# M700X.net
KiCad netlist of a schematic drawn in EAGLE
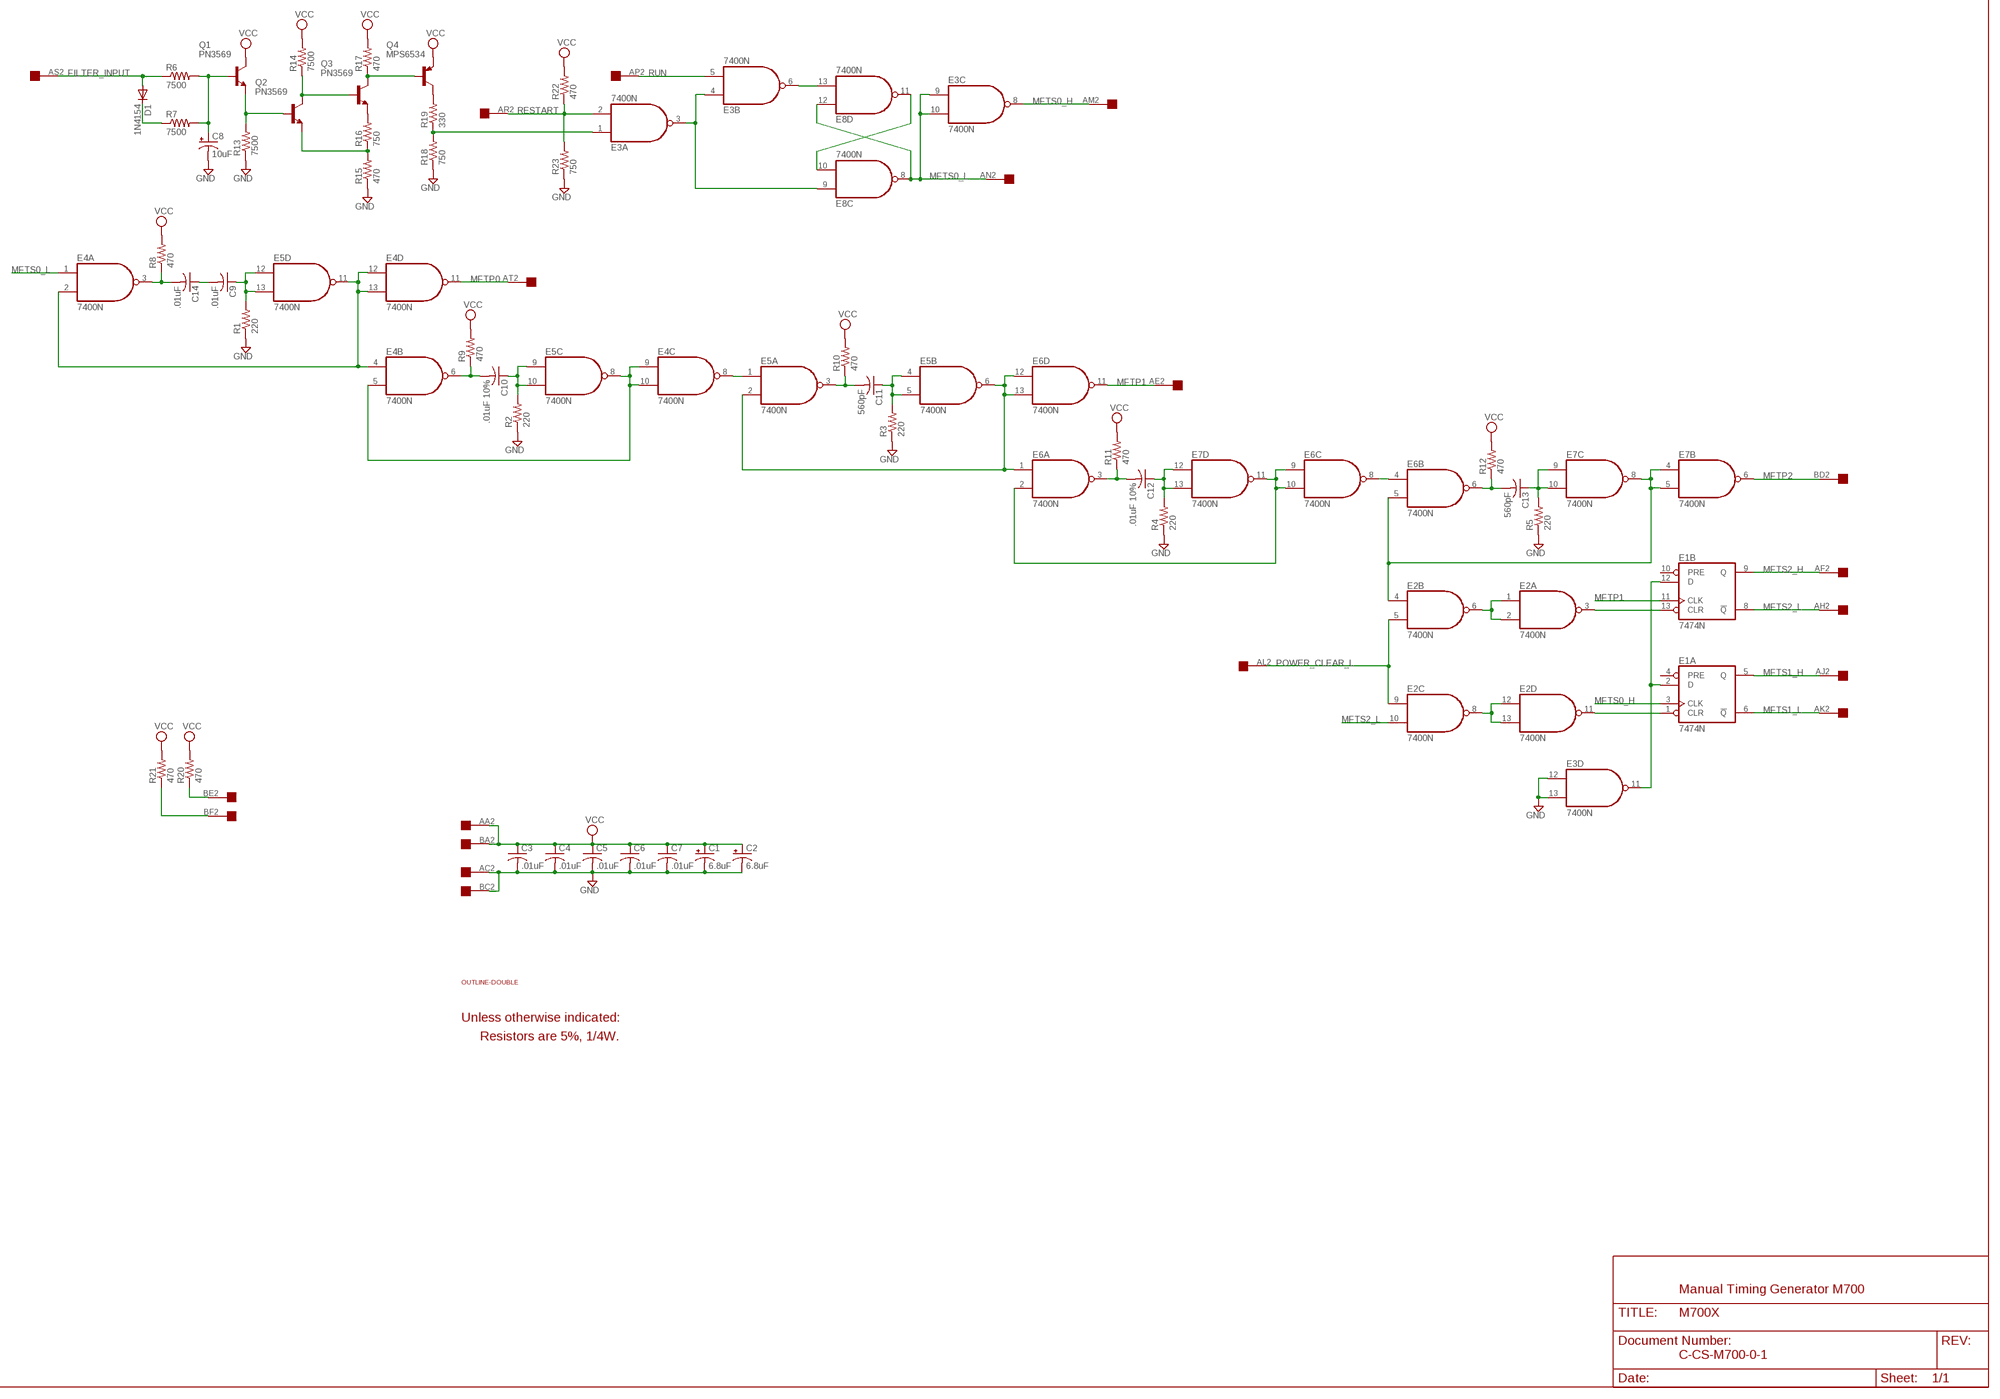
[diagram p0: schematic, sheet 1]

(export (version "E")
  (design (tool "Eeschema 10.0.6"))
  (components
    (comp (ref "C1")
      (value "6.8uF")
      (footprint "eagle-import:E12-8")
      (libsource (lib "eagle-import") (part "CPOL-USE20-8AXIAL"))
    )
    (comp (ref "C2")
      (value "6.8uF")
      (footprint "eagle-import:E12-8")
      (libsource (lib "eagle-import") (part "CPOL-USE20-8AXIAL"))
    )
    (comp (ref "C3")
      (value ".01uF")
      (footprint "eagle-import:C050-025X075")
      (libsource (lib "eagle-import") (part "C-US050-025X075"))
    )
    (comp (ref "C4")
      (value ".01uF")
      (footprint "eagle-import:C050-025X075")
      (libsource (lib "eagle-import") (part "C-US050-025X075"))
    )
    (comp (ref "C5")
      (value ".01uF")
      (footprint "eagle-import:C050-025X075")
      (libsource (lib "eagle-import") (part "C-US050-025X075"))
    )
    (comp (ref "C6")
      (value ".01uF")
      (footprint "eagle-import:C050-025X075")
      (libsource (lib "eagle-import") (part "C-US050-025X075"))
    )
    (comp (ref "C7")
      (value ".01uF")
      (footprint "eagle-import:C050-025X075")
      (libsource (lib "eagle-import") (part "C-US050-025X075"))
    )
    (comp (ref "C8")
      (value "10uF")
      (footprint "eagle-import:E12-8")
      (libsource (lib "eagle-import") (part "CPOL-USE20-8AXIAL"))
    )
    (comp (ref "C9")
      (value ".01uF")
      (footprint "eagle-import:C150-054X183")
      (libsource (lib "eagle-import") (part "C-US150-054X183"))
    )
    (comp (ref "C10")
      (value ".01uF 10%")
      (footprint "eagle-import:C150-054X183")
      (libsource (lib "eagle-import") (part "C-US150-054X183"))
    )
    (comp (ref "C11")
      (value "560pF")
      (footprint "eagle-import:C050-025X075")
      (libsource (lib "eagle-import") (part "C-US050-025X075"))
    )
    (comp (ref "C12")
      (value ".01uF 10%")
      (footprint "eagle-import:C150-054X183")
      (libsource (lib "eagle-import") (part "C-US150-054X183"))
    )
    (comp (ref "C13")
      (value "560pF")
      (footprint "eagle-import:C050-025X075")
      (libsource (lib "eagle-import") (part "C-US050-025X075"))
    )
    (comp (ref "C14")
      (value ".01uF")
      (footprint "eagle-import:C150-054X183")
      (libsource (lib "eagle-import") (part "C-US150-054X183"))
    )
    (comp (ref "D1")
      (value "1N4154")
      (footprint "eagle-import:DO35-10")
      (libsource (lib "eagle-import") (part "1N4148DO35-10"))
    )
    (comp (ref "E1")
      (value "7474N")
      (footprint "eagle-import:DIL14")
      (libsource (lib "eagle-import") (part "7474NS"))
    )
    (comp (ref "E2")
      (value "7400N")
      (footprint "eagle-import:DIL14")
      (libsource (lib "eagle-import") (part "7400N"))
    )
    (comp (ref "E3")
      (value "7400N")
      (footprint "eagle-import:DIL14")
      (libsource (lib "eagle-import") (part "7400N"))
    )
    (comp (ref "E4")
      (value "7400N")
      (footprint "eagle-import:DIL14")
      (libsource (lib "eagle-import") (part "7400N"))
    )
    (comp (ref "E5")
      (value "7400N")
      (footprint "eagle-import:DIL14")
      (libsource (lib "eagle-import") (part "7400N"))
    )
    (comp (ref "E6")
      (value "7400N")
      (footprint "eagle-import:DIL14")
      (libsource (lib "eagle-import") (part "7400N"))
    )
    (comp (ref "E7")
      (value "7400N")
      (footprint "eagle-import:DIL14")
      (libsource (lib "eagle-import") (part "7400N"))
    )
    (comp (ref "E8")
      (value "7400N")
      (footprint "eagle-import:DIL14")
      (libsource (lib "eagle-import") (part "7400N"))
    )
    (comp (ref "Q1")
      (value "PN3569")
      (footprint "eagle-import:TO5")
      (libsource (lib "eagle-import") (part "2N2102"))
    )
    (comp (ref "Q2")
      (value "PN3569")
      (footprint "eagle-import:TO5")
      (libsource (lib "eagle-import") (part "2N2102"))
    )
    (comp (ref "Q3")
      (value "PN3569")
      (footprint "eagle-import:TO5")
      (libsource (lib "eagle-import") (part "2N2102"))
    )
    (comp (ref "Q4")
      (value "MPS6534")
      (footprint "eagle-import:TO5")
      (libsource (lib "eagle-import") (part "2N2905"))
    )
    (comp (ref "R1")
      (value "220")
      (footprint "eagle-import:0207_10")
      (libsource (lib "eagle-import") (part "R-US_0207/10"))
    )
    (comp (ref "R2")
      (value "220")
      (footprint "eagle-import:0207_10")
      (libsource (lib "eagle-import") (part "R-US_0207/10"))
    )
    (comp (ref "R3")
      (value "220")
      (footprint "eagle-import:0207_10")
      (libsource (lib "eagle-import") (part "R-US_0207/10"))
    )
    (comp (ref "R4")
      (value "220")
      (footprint "eagle-import:0207_10")
      (libsource (lib "eagle-import") (part "R-US_0207/10"))
    )
    (comp (ref "R5")
      (value "220")
      (footprint "eagle-import:0207_10")
      (libsource (lib "eagle-import") (part "R-US_0207/10"))
    )
    (comp (ref "R6")
      (value "7500")
      (footprint "eagle-import:0207_10")
      (libsource (lib "eagle-import") (part "R-US_0207/10"))
    )
    (comp (ref "R7")
      (value "7500")
      (footprint "eagle-import:0207_10")
      (libsource (lib "eagle-import") (part "R-US_0207/10"))
    )
    (comp (ref "R8")
      (value "470")
      (footprint "eagle-import:0207_10")
      (libsource (lib "eagle-import") (part "R-US_0207/10"))
    )
    (comp (ref "R9")
      (value "470")
      (footprint "eagle-import:0207_10")
      (libsource (lib "eagle-import") (part "R-US_0207/10"))
    )
    (comp (ref "R10")
      (value "470")
      (footprint "eagle-import:0207_10")
      (libsource (lib "eagle-import") (part "R-US_0207/10"))
    )
    (comp (ref "R11")
      (value "470")
      (footprint "eagle-import:0207_10")
      (libsource (lib "eagle-import") (part "R-US_0207/10"))
    )
    (comp (ref "R12")
      (value "470")
      (footprint "eagle-import:0207_10")
      (libsource (lib "eagle-import") (part "R-US_0207/10"))
    )
    (comp (ref "R13")
      (value "7500")
      (footprint "eagle-import:0207_10")
      (libsource (lib "eagle-import") (part "R-US_0207/10"))
    )
    (comp (ref "R14")
      (value "7500")
      (footprint "eagle-import:0207_10")
      (libsource (lib "eagle-import") (part "R-US_0207/10"))
    )
    (comp (ref "R15")
      (value "470")
      (footprint "eagle-import:0207_10")
      (libsource (lib "eagle-import") (part "R-US_0207/10"))
    )
    (comp (ref "R16")
      (value "750")
      (footprint "eagle-import:0207_10")
      (libsource (lib "eagle-import") (part "R-US_0207/10"))
    )
    (comp (ref "R17")
      (value "470")
      (footprint "eagle-import:0207_10")
      (libsource (lib "eagle-import") (part "R-US_0207/10"))
    )
    (comp (ref "R18")
      (value "750")
      (footprint "eagle-import:0207_10")
      (libsource (lib "eagle-import") (part "R-US_0207/10"))
    )
    (comp (ref "R19")
      (value "330")
      (footprint "eagle-import:0207_10")
      (libsource (lib "eagle-import") (part "R-US_0207/10"))
    )
    (comp (ref "R20")
      (value "470")
      (footprint "eagle-import:0207_10")
      (libsource (lib "eagle-import") (part "R-US_0207/10"))
    )
    (comp (ref "R21")
      (value "470")
      (footprint "eagle-import:0207_10")
      (libsource (lib "eagle-import") (part "R-US_0207/10"))
    )
    (comp (ref "R22")
      (value "470")
      (footprint "eagle-import:0207_10")
      (libsource (lib "eagle-import") (part "R-US_0207/10"))
    )
    (comp (ref "R23")
      (value "750")
      (footprint "eagle-import:0207_10")
      (libsource (lib "eagle-import") (part "R-US_0207/10"))
    )
    (comp (ref "U$1")
      (value "DOUBLE")
      (footprint "eagle-import:EDGE-CON4")
      (libsource (lib "eagle-import") (part "DOUBLE"))
    )
    (comp (ref "U$2")
      (value "OUTLINE-DOUBLE")
      (footprint "eagle-import:DOUBLE")
      (libsource (lib "eagle-import") (part "OUTLINE-DOUBLE"))
    )
  )
  (nets
    (net (code "1") (name "/FILTER_INPUT") (class "Default")
      (node (ref "D1") (pin "A") (pinfunction "A_A") (pintype "passive"))
      (node (ref "R6") (pin "1") (pinfunction "1_1") (pintype "passive"))
      (node (ref "U$1") (pin "AS2") (pinfunction "1_AS2") (pintype "bidirectional"))
    )
    (net (code "2") (name "/MFTP0") (class "Default")
      (node (ref "E4") (pin "11") (pinfunction "O_11") (pintype "output"))
      (node (ref "U$1") (pin "AT2") (pinfunction "1_AT2") (pintype "bidirectional"))
    )
    (net (code "3") (name "/MFTP1") (class "Default")
      (node (ref "E1") (pin "11") (pinfunction "CLK_11") (pintype "input"))
      (node (ref "E6") (pin "11") (pinfunction "O_11") (pintype "output"))
      (node (ref "U$1") (pin "AE2") (pinfunction "1_AE2") (pintype "bidirectional"))
    )
    (net (code "4") (name "/MFTP2") (class "Default")
      (node (ref "E7") (pin "6") (pinfunction "O_6") (pintype "output"))
      (node (ref "U$1") (pin "BD2") (pinfunction "1_BD2") (pintype "bidirectional"))
    )
    (net (code "5") (name "/MFTS0_H") (class "Default")
      (node (ref "E1") (pin "3") (pinfunction "CLK_3") (pintype "input"))
      (node (ref "E3") (pin "8") (pinfunction "O_8") (pintype "output"))
      (node (ref "U$1") (pin "AM2") (pinfunction "1_AM2") (pintype "bidirectional"))
    )
    (net (code "6") (name "/MFTS0_L") (class "Default")
      (node (ref "E3") (pin "10") (pinfunction "I1_10") (pintype "input"))
      (node (ref "E3") (pin "9") (pinfunction "I0_9") (pintype "input"))
      (node (ref "E4") (pin "1") (pinfunction "I0_1") (pintype "input"))
      (node (ref "E8") (pin "12") (pinfunction "I0_12") (pintype "input"))
      (node (ref "E8") (pin "8") (pinfunction "O_8") (pintype "output"))
      (node (ref "U$1") (pin "AN2") (pinfunction "1_AN2") (pintype "bidirectional"))
    )
    (net (code "7") (name "/MFTS1_H") (class "Default")
      (node (ref "E1") (pin "5") (pinfunction "Q_5") (pintype "output"))
      (node (ref "U$1") (pin "AJ2") (pinfunction "1_AJ2") (pintype "bidirectional"))
    )
    (net (code "8") (name "/MFTS1_L") (class "Default")
      (node (ref "E1") (pin "6") (pinfunction "~{Q}_6") (pintype "output"))
      (node (ref "U$1") (pin "AK2") (pinfunction "1_AK2") (pintype "bidirectional"))
    )
    (net (code "9") (name "/MFTS2_H") (class "Default")
      (node (ref "E1") (pin "9") (pinfunction "Q_9") (pintype "output"))
      (node (ref "U$1") (pin "AF2") (pinfunction "1_AF2") (pintype "bidirectional"))
    )
    (net (code "10") (name "/MFTS2_L") (class "Default")
      (node (ref "E1") (pin "8") (pinfunction "~{Q}_8") (pintype "output"))
      (node (ref "E2") (pin "10") (pinfunction "I1_10") (pintype "input"))
      (node (ref "U$1") (pin "AH2") (pinfunction "1_AH2") (pintype "bidirectional"))
    )
    (net (code "11") (name "/POWER_CLEAR_L") (class "Default")
      (node (ref "E2") (pin "5") (pinfunction "I1_5") (pintype "input"))
      (node (ref "E2") (pin "9") (pinfunction "I0_9") (pintype "input"))
      (node (ref "U$1") (pin "AL2") (pinfunction "1_AL2") (pintype "bidirectional"))
    )
    (net (code "12") (name "/RESTART") (class "Default")
      (node (ref "E3") (pin "2") (pinfunction "I1_2") (pintype "input"))
      (node (ref "R22") (pin "1") (pinfunction "1_1") (pintype "passive"))
      (node (ref "R23") (pin "2") (pinfunction "2_2") (pintype "passive"))
      (node (ref "U$1") (pin "AR2") (pinfunction "1_AR2") (pintype "bidirectional"))
    )
    (net (code "13") (name "/RUN") (class "Default")
      (node (ref "E3") (pin "5") (pinfunction "I1_5") (pintype "input"))
      (node (ref "U$1") (pin "AP2") (pinfunction "1_AP2") (pintype "bidirectional"))
    )
    (net (code "14") (name "GND") (class "Default")
      (node (ref "C1") (pin "-") (pinfunction "-_-") (pintype "passive"))
      (node (ref "C2") (pin "-") (pinfunction "-_-") (pintype "passive"))
      (node (ref "C3") (pin "2") (pinfunction "2_2") (pintype "passive"))
      (node (ref "C4") (pin "2") (pinfunction "2_2") (pintype "passive"))
      (node (ref "C5") (pin "2") (pinfunction "2_2") (pintype "passive"))
      (node (ref "C6") (pin "2") (pinfunction "2_2") (pintype "passive"))
      (node (ref "C7") (pin "2") (pinfunction "2_2") (pintype "passive"))
      (node (ref "C8") (pin "-") (pinfunction "-_-") (pintype "passive"))
      (node (ref "E3") (pin "12") (pinfunction "I0_12") (pintype "input"))
      (node (ref "E3") (pin "13") (pinfunction "I1_13") (pintype "input"))
      (node (ref "R1") (pin "1") (pinfunction "1_1") (pintype "passive"))
      (node (ref "R13") (pin "1") (pinfunction "1_1") (pintype "passive"))
      (node (ref "R15") (pin "1") (pinfunction "1_1") (pintype "passive"))
      (node (ref "R18") (pin "1") (pinfunction "1_1") (pintype "passive"))
      (node (ref "R2") (pin "1") (pinfunction "1_1") (pintype "passive"))
      (node (ref "R23") (pin "1") (pinfunction "1_1") (pintype "passive"))
      (node (ref "R3") (pin "1") (pinfunction "1_1") (pintype "passive"))
      (node (ref "R4") (pin "1") (pinfunction "1_1") (pintype "passive"))
      (node (ref "R5") (pin "1") (pinfunction "1_1") (pintype "passive"))
      (node (ref "U$1") (pin "AC2") (pinfunction "1_AC2") (pintype "bidirectional"))
      (node (ref "U$1") (pin "BC2") (pinfunction "1_BC2") (pintype "bidirectional"))
    )
    (net (code "15") (name "Net-(C14-Pad1)") (class "Default")
      (node (ref "C14") (pin "1") (pinfunction "1_1") (pintype "passive"))
      (node (ref "C9") (pin "2") (pinfunction "2_2") (pintype "passive"))
    )
    (net (code "16") (name "Net-(D1-PadC)") (class "Default")
      (node (ref "D1") (pin "C") (pinfunction "C_C") (pintype "passive"))
      (node (ref "R7") (pin "1") (pinfunction "1_1") (pintype "passive"))
    )
    (net (code "17") (name "Net-(E1A-CLR)") (class "Default")
      (node (ref "E1") (pin "1") (pinfunction "CLR_1") (pintype "input"))
      (node (ref "E2") (pin "11") (pinfunction "O_11") (pintype "output"))
    )
    (net (code "18") (name "Net-(E1A-D)") (class "Default")
      (node (ref "E1") (pin "12") (pinfunction "D_12") (pintype "input"))
      (node (ref "E1") (pin "2") (pinfunction "D_2") (pintype "input"))
      (node (ref "E3") (pin "11") (pinfunction "O_11") (pintype "output"))
    )
    (net (code "19") (name "Net-(E1B-CLR)") (class "Default")
      (node (ref "E1") (pin "13") (pinfunction "CLR_13") (pintype "input"))
      (node (ref "E2") (pin "3") (pinfunction "O_3") (pintype "output"))
    )
    (net (code "20") (name "Net-(E2A-I0)") (class "Default")
      (node (ref "E2") (pin "1") (pinfunction "I0_1") (pintype "input"))
      (node (ref "E2") (pin "2") (pinfunction "I1_2") (pintype "input"))
      (node (ref "E2") (pin "6") (pinfunction "O_6") (pintype "output"))
    )
    (net (code "21") (name "Net-(E2B-I0)") (class "Default")
      (node (ref "E2") (pin "4") (pinfunction "I0_4") (pintype "input"))
      (node (ref "E6") (pin "5") (pinfunction "I1_5") (pintype "input"))
      (node (ref "E7") (pin "4") (pinfunction "I0_4") (pintype "input"))
      (node (ref "E7") (pin "5") (pinfunction "I1_5") (pintype "input"))
      (node (ref "E7") (pin "8") (pinfunction "O_8") (pintype "output"))
    )
    (net (code "22") (name "Net-(E2C-O)") (class "Default")
      (node (ref "E2") (pin "12") (pinfunction "I0_12") (pintype "input"))
      (node (ref "E2") (pin "13") (pinfunction "I1_13") (pintype "input"))
      (node (ref "E2") (pin "8") (pinfunction "O_8") (pintype "output"))
    )
    (net (code "23") (name "Net-(E3A-I0)") (class "Default")
      (node (ref "E3") (pin "1") (pinfunction "I0_1") (pintype "input"))
      (node (ref "R18") (pin "2") (pinfunction "2_2") (pintype "passive"))
      (node (ref "R19") (pin "1") (pinfunction "1_1") (pintype "passive"))
    )
    (net (code "24") (name "Net-(E3A-O)") (class "Default")
      (node (ref "E3") (pin "3") (pinfunction "O_3") (pintype "output"))
      (node (ref "E3") (pin "4") (pinfunction "I0_4") (pintype "input"))
      (node (ref "E8") (pin "9") (pinfunction "I0_9") (pintype "input"))
    )
    (net (code "25") (name "Net-(E3B-O)") (class "Default")
      (node (ref "E3") (pin "6") (pinfunction "O_6") (pintype "output"))
      (node (ref "E8") (pin "13") (pinfunction "I1_13") (pintype "input"))
    )
    (net (code "26") (name "Net-(E4A-I1)") (class "Default")
      (node (ref "E4") (pin "12") (pinfunction "I0_12") (pintype "input"))
      (node (ref "E4") (pin "13") (pinfunction "I1_13") (pintype "input"))
      (node (ref "E4") (pin "2") (pinfunction "I1_2") (pintype "input"))
      (node (ref "E4") (pin "4") (pinfunction "I0_4") (pintype "input"))
      (node (ref "E5") (pin "11") (pinfunction "O_11") (pintype "output"))
    )
    (net (code "27") (name "Net-(E4A-O)") (class "Default")
      (node (ref "C14") (pin "2") (pinfunction "2_2") (pintype "passive"))
      (node (ref "E4") (pin "3") (pinfunction "O_3") (pintype "output"))
      (node (ref "R8") (pin "1") (pinfunction "1_1") (pintype "passive"))
    )
    (net (code "28") (name "Net-(E4B-I1)") (class "Default")
      (node (ref "E4") (pin "10") (pinfunction "I1_10") (pintype "input"))
      (node (ref "E4") (pin "5") (pinfunction "I1_5") (pintype "input"))
      (node (ref "E4") (pin "9") (pinfunction "I0_9") (pintype "input"))
      (node (ref "E5") (pin "8") (pinfunction "O_8") (pintype "output"))
    )
    (net (code "29") (name "Net-(E4B-O)") (class "Default")
      (node (ref "C10") (pin "2") (pinfunction "2_2") (pintype "passive"))
      (node (ref "E4") (pin "6") (pinfunction "O_6") (pintype "output"))
      (node (ref "R9") (pin "1") (pinfunction "1_1") (pintype "passive"))
    )
    (net (code "30") (name "Net-(E4C-O)") (class "Default")
      (node (ref "E4") (pin "8") (pinfunction "O_8") (pintype "output"))
      (node (ref "E5") (pin "1") (pinfunction "I0_1") (pintype "input"))
    )
    (net (code "31") (name "Net-(E5A-I1)") (class "Default")
      (node (ref "E5") (pin "2") (pinfunction "I1_2") (pintype "input"))
      (node (ref "E5") (pin "6") (pinfunction "O_6") (pintype "output"))
      (node (ref "E6") (pin "1") (pinfunction "I0_1") (pintype "input"))
      (node (ref "E6") (pin "12") (pinfunction "I0_12") (pintype "input"))
      (node (ref "E6") (pin "13") (pinfunction "I1_13") (pintype "input"))
    )
    (net (code "32") (name "Net-(E5A-O)") (class "Default")
      (node (ref "C11") (pin "2") (pinfunction "2_2") (pintype "passive"))
      (node (ref "E5") (pin "3") (pinfunction "O_3") (pintype "output"))
      (node (ref "R10") (pin "1") (pinfunction "1_1") (pintype "passive"))
    )
    (net (code "33") (name "Net-(E5B-I0)") (class "Default")
      (node (ref "C11") (pin "1") (pinfunction "1_1") (pintype "passive"))
      (node (ref "E5") (pin "4") (pinfunction "I0_4") (pintype "input"))
      (node (ref "E5") (pin "5") (pinfunction "I1_5") (pintype "input"))
      (node (ref "R3") (pin "2") (pinfunction "2_2") (pintype "passive"))
    )
    (net (code "34") (name "Net-(E5C-I0)") (class "Default")
      (node (ref "C10") (pin "1") (pinfunction "1_1") (pintype "passive"))
      (node (ref "E5") (pin "10") (pinfunction "I1_10") (pintype "input"))
      (node (ref "E5") (pin "9") (pinfunction "I0_9") (pintype "input"))
      (node (ref "R2") (pin "2") (pinfunction "2_2") (pintype "passive"))
    )
    (net (code "35") (name "Net-(E5D-I0)") (class "Default")
      (node (ref "C9") (pin "1") (pinfunction "1_1") (pintype "passive"))
      (node (ref "E5") (pin "12") (pinfunction "I0_12") (pintype "input"))
      (node (ref "E5") (pin "13") (pinfunction "I1_13") (pintype "input"))
      (node (ref "R1") (pin "2") (pinfunction "2_2") (pintype "passive"))
    )
    (net (code "36") (name "Net-(E6A-I1)") (class "Default")
      (node (ref "E6") (pin "10") (pinfunction "I1_10") (pintype "input"))
      (node (ref "E6") (pin "2") (pinfunction "I1_2") (pintype "input"))
      (node (ref "E6") (pin "9") (pinfunction "I0_9") (pintype "input"))
      (node (ref "E7") (pin "11") (pinfunction "O_11") (pintype "output"))
    )
    (net (code "37") (name "Net-(E6A-O)") (class "Default")
      (node (ref "C12") (pin "2") (pinfunction "2_2") (pintype "passive"))
      (node (ref "E6") (pin "3") (pinfunction "O_3") (pintype "output"))
      (node (ref "R11") (pin "1") (pinfunction "1_1") (pintype "passive"))
    )
    (net (code "38") (name "Net-(E6B-I0)") (class "Default")
      (node (ref "E6") (pin "4") (pinfunction "I0_4") (pintype "input"))
      (node (ref "E6") (pin "8") (pinfunction "O_8") (pintype "output"))
    )
    (net (code "39") (name "Net-(E6B-O)") (class "Default")
      (node (ref "C13") (pin "2") (pinfunction "2_2") (pintype "passive"))
      (node (ref "E6") (pin "6") (pinfunction "O_6") (pintype "output"))
      (node (ref "R12") (pin "1") (pinfunction "1_1") (pintype "passive"))
    )
    (net (code "40") (name "Net-(E7C-I0)") (class "Default")
      (node (ref "C13") (pin "1") (pinfunction "1_1") (pintype "passive"))
      (node (ref "E7") (pin "10") (pinfunction "I1_10") (pintype "input"))
      (node (ref "E7") (pin "9") (pinfunction "I0_9") (pintype "input"))
      (node (ref "R5") (pin "2") (pinfunction "2_2") (pintype "passive"))
    )
    (net (code "41") (name "Net-(E7D-I0)") (class "Default")
      (node (ref "C12") (pin "1") (pinfunction "1_1") (pintype "passive"))
      (node (ref "E7") (pin "12") (pinfunction "I0_12") (pintype "input"))
      (node (ref "E7") (pin "13") (pinfunction "I1_13") (pintype "input"))
      (node (ref "R4") (pin "2") (pinfunction "2_2") (pintype "passive"))
    )
    (net (code "42") (name "Net-(E8C-I1)") (class "Default")
      (node (ref "E8") (pin "10") (pinfunction "I1_10") (pintype "input"))
      (node (ref "E8") (pin "11") (pinfunction "O_11") (pintype "output"))
    )
    (net (code "43") (name "Net-(Q1-B)") (class "Default")
      (node (ref "C8") (pin "+") (pinfunction "+_+") (pintype "passive"))
      (node (ref "Q1") (pin "2") (pinfunction "B_2") (pintype "passive"))
      (node (ref "R6") (pin "2") (pinfunction "2_2") (pintype "passive"))
      (node (ref "R7") (pin "2") (pinfunction "2_2") (pintype "passive"))
    )
    (net (code "44") (name "Net-(Q1-E)") (class "Default")
      (node (ref "Q1") (pin "1") (pinfunction "E_1") (pintype "passive"))
      (node (ref "Q2") (pin "2") (pinfunction "B_2") (pintype "passive"))
      (node (ref "R13") (pin "2") (pinfunction "2_2") (pintype "passive"))
    )
    (net (code "45") (name "Net-(Q2-C)") (class "Default")
      (node (ref "Q2") (pin "3") (pinfunction "C_3") (pintype "passive"))
      (node (ref "Q3") (pin "2") (pinfunction "B_2") (pintype "passive"))
      (node (ref "R14") (pin "1") (pinfunction "1_1") (pintype "passive"))
    )
    (net (code "46") (name "Net-(Q2-E)") (class "Default")
      (node (ref "Q2") (pin "1") (pinfunction "E_1") (pintype "passive"))
      (node (ref "R15") (pin "2") (pinfunction "2_2") (pintype "passive"))
      (node (ref "R16") (pin "1") (pinfunction "1_1") (pintype "passive"))
    )
    (net (code "47") (name "Net-(Q3-C)") (class "Default")
      (node (ref "Q3") (pin "3") (pinfunction "C_3") (pintype "passive"))
      (node (ref "Q4") (pin "2") (pinfunction "B_2") (pintype "passive"))
      (node (ref "R17") (pin "1") (pinfunction "1_1") (pintype "passive"))
    )
    (net (code "48") (name "Net-(Q3-E)") (class "Default")
      (node (ref "Q3") (pin "1") (pinfunction "E_1") (pintype "passive"))
      (node (ref "R16") (pin "2") (pinfunction "2_2") (pintype "passive"))
    )
    (net (code "49") (name "Net-(Q4-C)") (class "Default")
      (node (ref "Q4") (pin "3") (pinfunction "C_3") (pintype "passive"))
      (node (ref "R19") (pin "2") (pinfunction "2_2") (pintype "passive"))
    )
    (net (code "50") (name "Net-(U$1AT-1)") (class "Default")
      (node (ref "R20") (pin "1") (pinfunction "1_1") (pintype "passive"))
      (node (ref "U$1") (pin "BE2") (pinfunction "1_BE2") (pintype "bidirectional"))
    )
    (net (code "51") (name "Net-(U$1AV-1)") (class "Default")
      (node (ref "R21") (pin "1") (pinfunction "1_1") (pintype "passive"))
      (node (ref "U$1") (pin "BF2") (pinfunction "1_BF2") (pintype "bidirectional"))
    )
    (net (code "52") (name "VCC") (class "Default")
      (node (ref "C1") (pin "+") (pinfunction "+_+") (pintype "passive"))
      (node (ref "C2") (pin "+") (pinfunction "+_+") (pintype "passive"))
      (node (ref "C3") (pin "1") (pinfunction "1_1") (pintype "passive"))
      (node (ref "C4") (pin "1") (pinfunction "1_1") (pintype "passive"))
      (node (ref "C5") (pin "1") (pinfunction "1_1") (pintype "passive"))
      (node (ref "C6") (pin "1") (pinfunction "1_1") (pintype "passive"))
      (node (ref "C7") (pin "1") (pinfunction "1_1") (pintype "passive"))
      (node (ref "Q1") (pin "3") (pinfunction "C_3") (pintype "passive"))
      (node (ref "Q4") (pin "1") (pinfunction "E_1") (pintype "passive"))
      (node (ref "R10") (pin "2") (pinfunction "2_2") (pintype "passive"))
      (node (ref "R11") (pin "2") (pinfunction "2_2") (pintype "passive"))
      (node (ref "R12") (pin "2") (pinfunction "2_2") (pintype "passive"))
      (node (ref "R14") (pin "2") (pinfunction "2_2") (pintype "passive"))
      (node (ref "R17") (pin "2") (pinfunction "2_2") (pintype "passive"))
      (node (ref "R20") (pin "2") (pinfunction "2_2") (pintype "passive"))
      (node (ref "R21") (pin "2") (pinfunction "2_2") (pintype "passive"))
      (node (ref "R22") (pin "2") (pinfunction "2_2") (pintype "passive"))
      (node (ref "R8") (pin "2") (pinfunction "2_2") (pintype "passive"))
      (node (ref "R9") (pin "2") (pinfunction "2_2") (pintype "passive"))
      (node (ref "U$1") (pin "AA2") (pinfunction "1_AA2") (pintype "bidirectional"))
      (node (ref "U$1") (pin "BA2") (pinfunction "1_BA2") (pintype "bidirectional"))
    )
    (net (code "53") (name "unconnected-(E1A-PRE-Pad4)") (class "Default")
      (node (ref "E1") (pin "4") (pinfunction "PRE_4") (pintype "input"))
    )
    (net (code "54") (name "unconnected-(E1B-PRE-Pad10)") (class "Default")
      (node (ref "E1") (pin "10") (pinfunction "PRE_10") (pintype "input"))
    )
  )
)
